# connector.net
KiCad netlist of a schematic drawn in Altium Designer
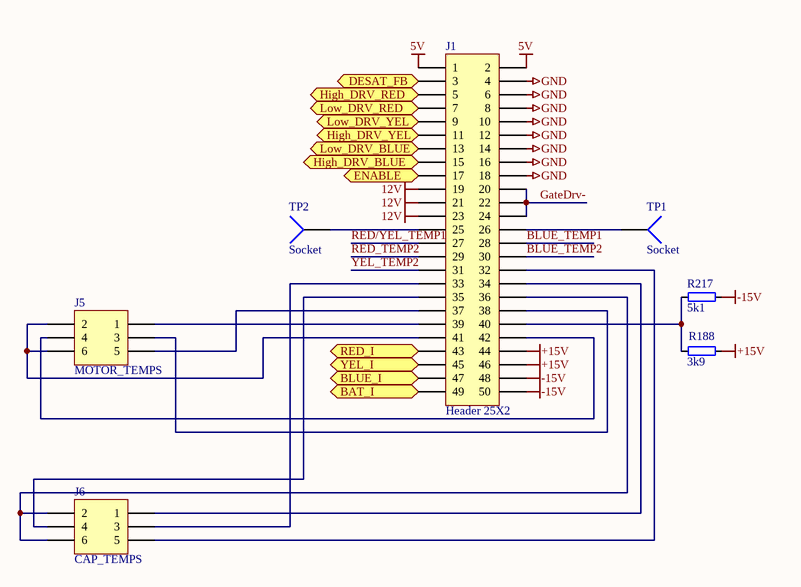
[diagram p0: connector.SchDoc]

(export (version "E")
  (design (tool "Eeschema 10.0.6"))
  (components
    (comp (ref "J1")
      (value "Header 25X2")
      (footprint "HDR2X25")
      (description "Header, 25-Pin, Dual row")
      (fields (field (name "PUBLISHER") "Altium Limited"))
      (libsource (lib "Miscellaneous Connectors") (part "Header 25X2"))
    )
    (comp (ref "J5")
      (value "MOTOR_TEMPS")
      (footprint "HDR2X3")
      (description "Header, 3-Pin, Dual row")
      (fields (field (name "PUBLISHER") "Altium Limited"))
      (libsource (lib "Miscellaneous Connectors") (part "Header 3X2"))
    )
    (comp (ref "J6")
      (value "CAP_TEMPS")
      (footprint "HDR2X3")
      (description "Header, 3-Pin, Dual row")
      (fields (field (name "PUBLISHER") "Altium Limited"))
      (libsource (lib "Miscellaneous Connectors") (part "Header 3X2"))
    )
    (comp (ref "R188")
      (value "3k9")
      (footprint "0402")
      (description "Resistor")
      (libsource (lib "Schematic Library") (part "RESISTOR"))
    )
    (comp (ref "R217")
      (value "5k1")
      (footprint "0402")
      (description "Resistor")
      (libsource (lib "Schematic Library") (part "RESISTOR"))
    )
    (comp (ref "TP1")
      (value "Socket")
      (footprint "PIN1")
      (fields (field (name "PUBLISHER") "Altium Limited"))
      (libsource (lib "Miscellaneous Connectors") (part "Socket"))
    )
    (comp (ref "TP2")
      (value "Socket")
      (footprint "PIN1")
      (fields (field (name "PUBLISHER") "Altium Limited"))
      (libsource (lib "Miscellaneous Connectors") (part "Socket"))
    )
  )
  (nets
    (net (code "1") (name "+15V") (class "Default")
      (node (ref "J1") (pin "44") (pinfunction "44_44") (pintype "passive"))
      (node (ref "J1") (pin "46") (pinfunction "46_46") (pintype "passive"))
      (node (ref "R188") (pin "2") (pintype "passive"))
    )
    (net (code "2") (name "-15V") (class "Default")
      (node (ref "J1") (pin "48") (pinfunction "48_48") (pintype "passive"))
      (node (ref "J1") (pin "50") (pinfunction "50_50") (pintype "passive"))
      (node (ref "R217") (pin "2") (pintype "passive"))
    )
    (net (code "3") (name "/BAT_I") (class "Default")
      (node (ref "J1") (pin "49") (pinfunction "49_49") (pintype "passive"))
    )
    (net (code "4") (name "/BLUE_I") (class "Default")
      (node (ref "J1") (pin "47") (pinfunction "47_47") (pintype "passive"))
    )
    (net (code "5") (name "/BLUE_TEMP1") (class "Default")
      (node (ref "J1") (pin "28") (pinfunction "28_28") (pintype "passive"))
    )
    (net (code "6") (name "/BLUE_TEMP2") (class "Default")
      (node (ref "J1") (pin "30") (pinfunction "30_30") (pintype "passive"))
    )
    (net (code "7") (name "/DESAT_FB") (class "Default")
      (node (ref "J1") (pin "3") (pinfunction "3_3") (pintype "passive"))
    )
    (net (code "8") (name "/ENABLE") (class "Default")
      (node (ref "J1") (pin "17") (pinfunction "17_17") (pintype "passive"))
    )
    (net (code "9") (name "/GateDrv-") (class "Default")
      (node (ref "J1") (pin "20") (pinfunction "20_20") (pintype "passive"))
      (node (ref "J1") (pin "22") (pinfunction "22_22") (pintype "passive"))
      (node (ref "J1") (pin "24") (pinfunction "24_24") (pintype "passive"))
    )
    (net (code "10") (name "/High_DRV_BLUE") (class "Default")
      (node (ref "J1") (pin "15") (pinfunction "15_15") (pintype "passive"))
    )
    (net (code "11") (name "/High_DRV_RED") (class "Default")
      (node (ref "J1") (pin "5") (pinfunction "5_5") (pintype "passive"))
    )
    (net (code "12") (name "/High_DRV_YEL") (class "Default")
      (node (ref "J1") (pin "11") (pinfunction "11_11") (pintype "passive"))
    )
    (net (code "13") (name "/Low_DRV_BLUE") (class "Default")
      (node (ref "J1") (pin "13") (pinfunction "13_13") (pintype "passive"))
    )
    (net (code "14") (name "/Low_DRV_RED") (class "Default")
      (node (ref "J1") (pin "7") (pinfunction "7_7") (pintype "passive"))
    )
    (net (code "15") (name "/Low_DRV_YEL") (class "Default")
      (node (ref "J1") (pin "9") (pinfunction "9_9") (pintype "passive"))
    )
    (net (code "16") (name "/RED_I") (class "Default")
      (node (ref "J1") (pin "43") (pinfunction "43_43") (pintype "passive"))
    )
    (net (code "17") (name "/RED_TEMP2") (class "Default")
      (node (ref "J1") (pin "29") (pinfunction "29_29") (pintype "passive"))
    )
    (net (code "18") (name "/RED{slash}YEL_TEMP1") (class "Default")
      (node (ref "J1") (pin "27") (pinfunction "27_27") (pintype "passive"))
    )
    (net (code "19") (name "/YEL_I") (class "Default")
      (node (ref "J1") (pin "45") (pinfunction "45_45") (pintype "passive"))
    )
    (net (code "20") (name "/YEL_TEMP2") (class "Default")
      (node (ref "J1") (pin "31") (pinfunction "31_31") (pintype "passive"))
    )
    (net (code "21") (name "5V") (class "Default")
      (node (ref "J1") (pin "1") (pinfunction "1_1") (pintype "passive"))
      (node (ref "J1") (pin "2") (pinfunction "2_2") (pintype "passive"))
    )
    (net (code "22") (name "12V") (class "Default")
      (node (ref "J1") (pin "19") (pinfunction "19_19") (pintype "passive"))
      (node (ref "J1") (pin "21") (pinfunction "21_21") (pintype "passive"))
      (node (ref "J1") (pin "23") (pinfunction "23_23") (pintype "passive"))
    )
    (net (code "23") (name "GND") (class "Default")
      (node (ref "J1") (pin "10") (pinfunction "10_10") (pintype "passive"))
      (node (ref "J1") (pin "12") (pinfunction "12_12") (pintype "passive"))
      (node (ref "J1") (pin "14") (pinfunction "14_14") (pintype "passive"))
      (node (ref "J1") (pin "16") (pinfunction "16_16") (pintype "passive"))
      (node (ref "J1") (pin "18") (pinfunction "18_18") (pintype "passive"))
      (node (ref "J1") (pin "4") (pinfunction "4_4") (pintype "passive"))
      (node (ref "J1") (pin "6") (pinfunction "6_6") (pintype "passive"))
      (node (ref "J1") (pin "8") (pinfunction "8_8") (pintype "passive"))
    )
    (net (code "24") (name "Net-(J1-Pad25)") (class "Default")
      (node (ref "J1") (pin "25") (pinfunction "25_25") (pintype "passive"))
      (node (ref "TP2") (pin "1") (pinfunction "1_1") (pintype "passive"))
    )
    (net (code "25") (name "Net-(J1-Pad26)") (class "Default")
      (node (ref "J1") (pin "26") (pinfunction "26_26") (pintype "passive"))
      (node (ref "TP1") (pin "1") (pinfunction "1_1") (pintype "passive"))
    )
    (net (code "26") (name "Net-(J1-Pad32)") (class "Default")
      (node (ref "J1") (pin "32") (pinfunction "32_32") (pintype "passive"))
      (node (ref "J6") (pin "5") (pinfunction "5_5") (pintype "passive"))
    )
    (net (code "27") (name "Net-(J1-Pad33)") (class "Default")
      (node (ref "J1") (pin "33") (pinfunction "33_33") (pintype "passive"))
      (node (ref "J6") (pin "3") (pinfunction "3_3") (pintype "passive"))
    )
    (net (code "28") (name "Net-(J1-Pad34)") (class "Default")
      (node (ref "J1") (pin "34") (pinfunction "34_34") (pintype "passive"))
      (node (ref "J6") (pin "1") (pinfunction "1_1") (pintype "passive"))
    )
    (net (code "29") (name "Net-(J1-Pad35)") (class "Default")
      (node (ref "J1") (pin "35") (pinfunction "35_35") (pintype "passive"))
      (node (ref "J6") (pin "4") (pinfunction "4_4") (pintype "passive"))
    )
    (net (code "30") (name "Net-(J1-Pad36)") (class "Default")
      (node (ref "J1") (pin "36") (pinfunction "36_36") (pintype "passive"))
      (node (ref "J6") (pin "2") (pinfunction "2_2") (pintype "passive"))
      (node (ref "J6") (pin "6") (pinfunction "6_6") (pintype "passive"))
    )
    (net (code "31") (name "Net-(J1-Pad37)") (class "Default")
      (node (ref "J1") (pin "37") (pinfunction "37_37") (pintype "passive"))
      (node (ref "J5") (pin "5") (pinfunction "5_5") (pintype "passive"))
    )
    (net (code "32") (name "Net-(J1-Pad38)") (class "Default")
      (node (ref "J1") (pin "38") (pinfunction "38_38") (pintype "passive"))
      (node (ref "J5") (pin "3") (pinfunction "3_3") (pintype "passive"))
    )
    (net (code "33") (name "Net-(J1-Pad39)") (class "Default")
      (node (ref "J1") (pin "39") (pinfunction "39_39") (pintype "passive"))
      (node (ref "J5") (pin "1") (pinfunction "1_1") (pintype "passive"))
    )
    (net (code "34") (name "Net-(J1-Pad40)") (class "Default")
      (node (ref "J1") (pin "40") (pinfunction "40_40") (pintype "passive"))
      (node (ref "R188") (pin "1") (pintype "passive"))
      (node (ref "R217") (pin "1") (pintype "passive"))
    )
    (net (code "35") (name "Net-(J1-Pad41)") (class "Default")
      (node (ref "J1") (pin "41") (pinfunction "41_41") (pintype "passive"))
      (node (ref "J5") (pin "2") (pinfunction "2_2") (pintype "passive"))
      (node (ref "J5") (pin "6") (pinfunction "6_6") (pintype "passive"))
    )
    (net (code "36") (name "Net-(J1-Pad42)") (class "Default")
      (node (ref "J1") (pin "42") (pinfunction "42_42") (pintype "passive"))
      (node (ref "J5") (pin "4") (pinfunction "4_4") (pintype "passive"))
    )
  )
)
